# Version1.net
KiCad netlist of a schematic drawn in EAGLE
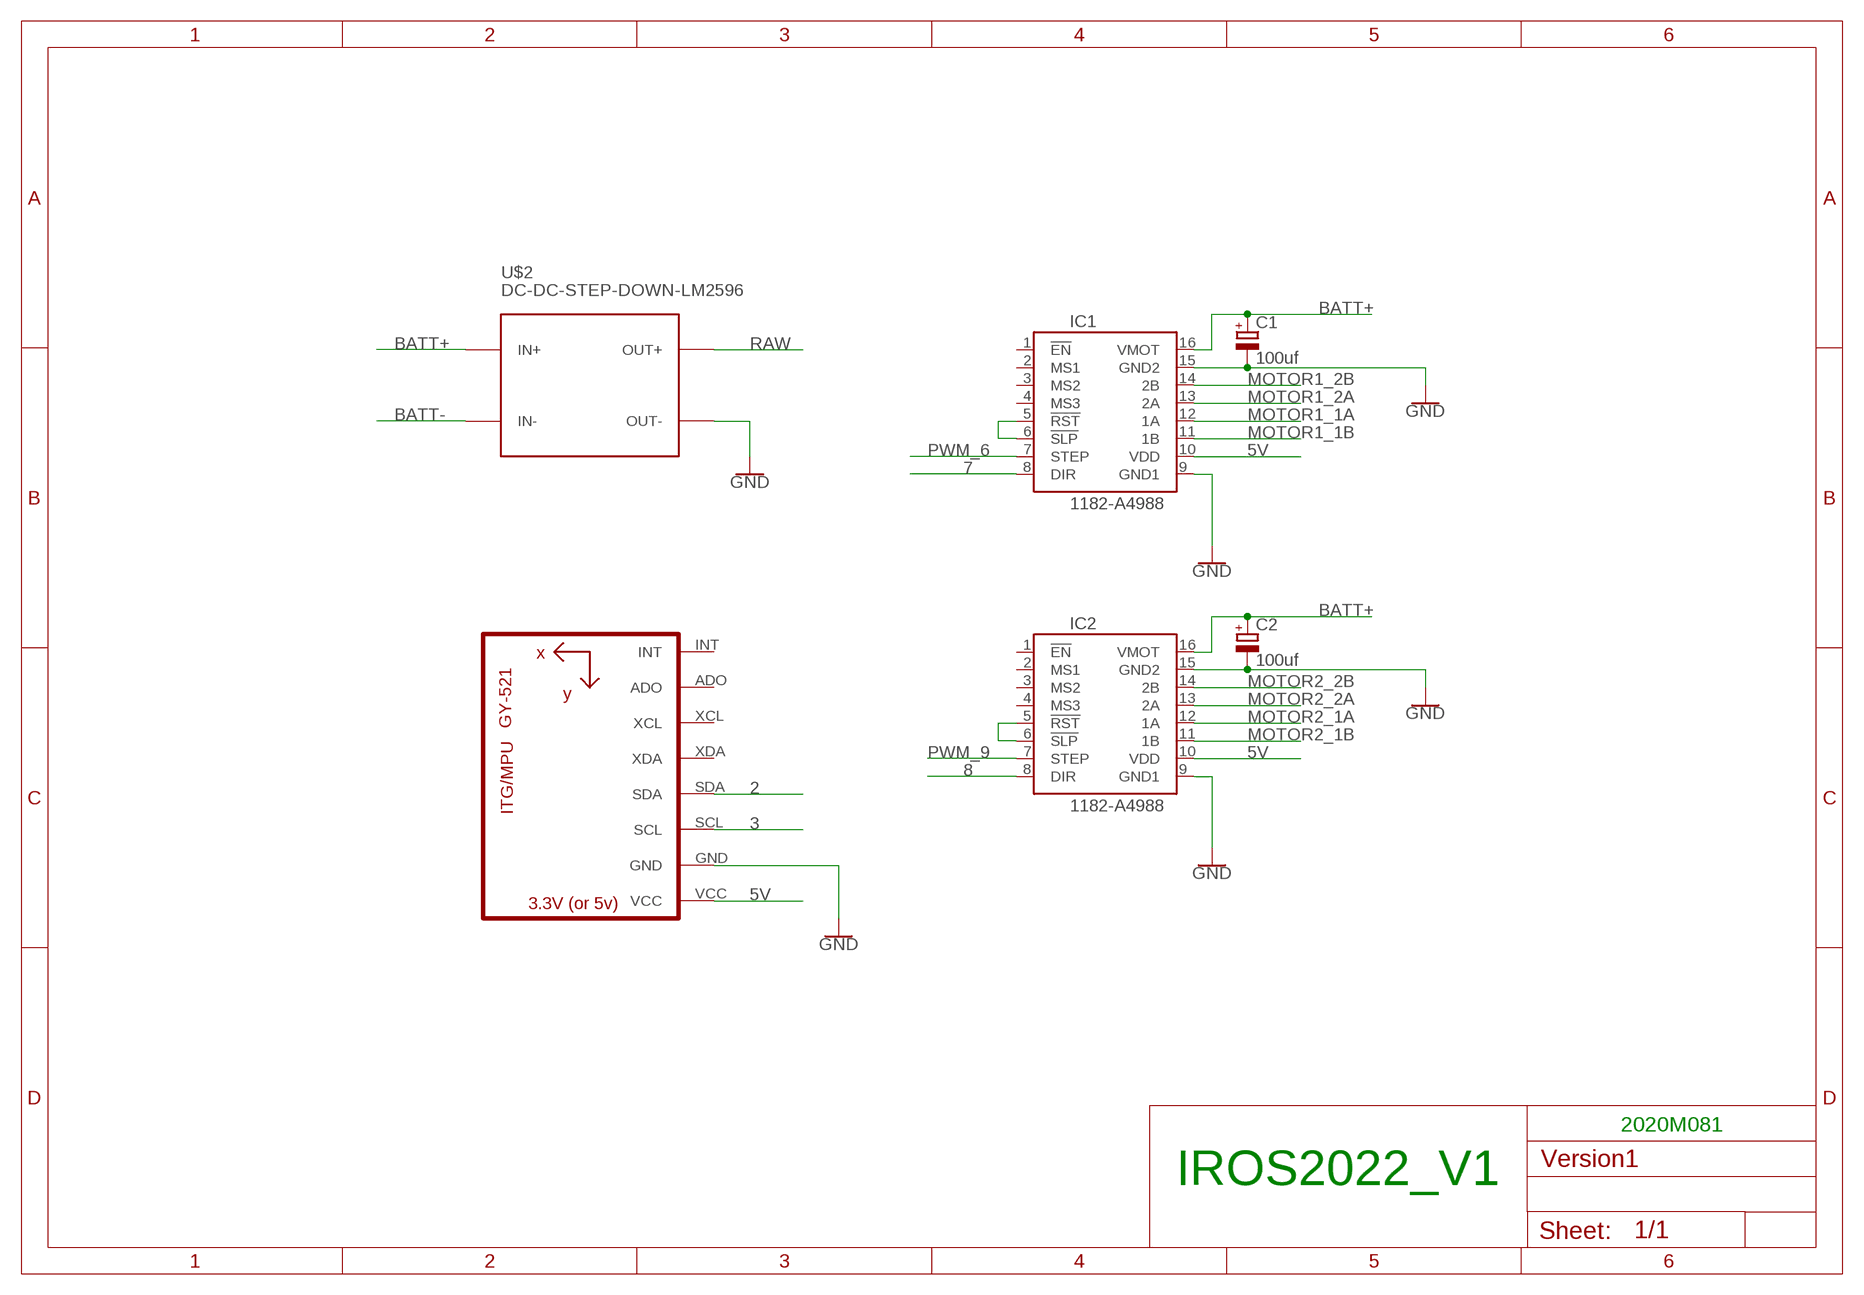
[diagram p0: schematic, sheet 1]

(export (version "E")
  (design (tool "Eeschema 10.0.6"))
  (components
    (comp (ref "C1")
      (value "100uf")
      (footprint "eagle-import:E5-10,5")
      (libsource (lib "eagle-import") (part "CPOL-EUE5-10.5"))
    )
    (comp (ref "C2")
      (value "100uf")
      (footprint "eagle-import:E5-10,5")
      (libsource (lib "eagle-import") (part "CPOL-EUE5-10.5"))
    )
    (comp (ref "IC1")
      (value "1182-A4988")
      (footprint "eagle-import:A4988")
      (libsource (lib "eagle-import") (part "1182-A4988"))
    )
    (comp (ref "IC2")
      (value "1182-A4988")
      (footprint "eagle-import:A4988")
      (libsource (lib "eagle-import") (part "1182-A4988"))
    )
    (comp (ref "U$2")
      (value "DC-DC-STEP-DOWN-LM2596")
      (footprint "eagle-import:DC-DC-STEP-DOWN-LM2596")
      (libsource (lib "eagle-import") (part "DC-DC-STEP-DOWN-LM2596"))
    )
    (comp (ref "U1")
      (value "GY-521MPU6050")
      (footprint "eagle-import:GY-521")
      (libsource (lib "eagle-import") (part "GY-521MPU6050"))
    )
  )
  (nets
    (net (code "1") (name "/2") (class "Default")
      (node (ref "U1") (pin "SDA") (pinfunction "SDA_SDA") (pintype "bidirectional"))
    )
    (net (code "2") (name "/3") (class "Default")
      (node (ref "U1") (pin "SCL") (pinfunction "SCL_SCL") (pintype "bidirectional"))
    )
    (net (code "3") (name "/5V") (class "Default")
      (node (ref "IC1") (pin "10") (pinfunction "VDD_10") (pintype "power_in"))
      (node (ref "IC2") (pin "10") (pinfunction "VDD_10") (pintype "power_in"))
      (node (ref "U1") (pin "VCC") (pinfunction "VCC_VCC") (pintype "bidirectional"))
    )
    (net (code "4") (name "/7") (class "Default")
      (node (ref "IC1") (pin "8") (pinfunction "DIR_8") (pintype "input"))
    )
    (net (code "5") (name "/8") (class "Default")
      (node (ref "IC2") (pin "8") (pinfunction "DIR_8") (pintype "input"))
    )
    (net (code "6") (name "/BATT+") (class "Default")
      (node (ref "C1") (pin "+") (pinfunction "+_+") (pintype "passive"))
      (node (ref "C2") (pin "+") (pinfunction "+_+") (pintype "passive"))
      (node (ref "IC1") (pin "16") (pinfunction "VMOT_16") (pintype "power_in"))
      (node (ref "IC2") (pin "16") (pinfunction "VMOT_16") (pintype "power_in"))
      (node (ref "U$2") (pin "IN+") (pinfunction "IN+_IN+") (pintype "bidirectional"))
    )
    (net (code "7") (name "/BATT-") (class "Default")
      (node (ref "U$2") (pin "IN-") (pinfunction "IN-_IN-") (pintype "bidirectional"))
    )
    (net (code "8") (name "/MOTOR1_1A") (class "Default")
      (node (ref "IC1") (pin "12") (pinfunction "1A_12") (pintype "output"))
    )
    (net (code "9") (name "/MOTOR1_1B") (class "Default")
      (node (ref "IC1") (pin "11") (pinfunction "1B_11") (pintype "output"))
    )
    (net (code "10") (name "/MOTOR1_2A") (class "Default")
      (node (ref "IC1") (pin "13") (pinfunction "2A_13") (pintype "output"))
    )
    (net (code "11") (name "/MOTOR1_2B") (class "Default")
      (node (ref "IC1") (pin "14") (pinfunction "2B_14") (pintype "output"))
    )
    (net (code "12") (name "/MOTOR2_1A") (class "Default")
      (node (ref "IC2") (pin "12") (pinfunction "1A_12") (pintype "output"))
    )
    (net (code "13") (name "/MOTOR2_1B") (class "Default")
      (node (ref "IC2") (pin "11") (pinfunction "1B_11") (pintype "output"))
    )
    (net (code "14") (name "/MOTOR2_2A") (class "Default")
      (node (ref "IC2") (pin "13") (pinfunction "2A_13") (pintype "output"))
    )
    (net (code "15") (name "/MOTOR2_2B") (class "Default")
      (node (ref "IC2") (pin "14") (pinfunction "2B_14") (pintype "output"))
    )
    (net (code "16") (name "/PWM_6") (class "Default")
      (node (ref "IC1") (pin "7") (pinfunction "STEP_7") (pintype "input"))
    )
    (net (code "17") (name "/PWM_9") (class "Default")
      (node (ref "IC2") (pin "7") (pinfunction "STEP_7") (pintype "input"))
    )
    (net (code "18") (name "/RAW") (class "Default")
      (node (ref "U$2") (pin "OUT+") (pinfunction "OUT+_OUT+") (pintype "bidirectional"))
    )
    (net (code "19") (name "GND") (class "Default")
      (node (ref "C1") (pin "-") (pinfunction "-_-") (pintype "passive"))
      (node (ref "C2") (pin "-") (pinfunction "-_-") (pintype "passive"))
      (node (ref "IC1") (pin "15") (pinfunction "GND2_15") (pintype "power_in"))
      (node (ref "IC1") (pin "9") (pinfunction "GND1_9") (pintype "power_in"))
      (node (ref "IC2") (pin "15") (pinfunction "GND2_15") (pintype "power_in"))
      (node (ref "IC2") (pin "9") (pinfunction "GND1_9") (pintype "power_in"))
      (node (ref "U$2") (pin "OUT-") (pinfunction "OUT-_OUT-") (pintype "bidirectional"))
      (node (ref "U1") (pin "GND") (pinfunction "GND_GND") (pintype "bidirectional"))
    )
    (net (code "20") (name "Net-(IC1-~{RST})") (class "Default")
      (node (ref "IC1") (pin "5") (pinfunction "~{RST}_5") (pintype "passive"))
      (node (ref "IC1") (pin "6") (pinfunction "~{SLP}_6") (pintype "passive"))
    )
    (net (code "21") (name "Net-(IC2-~{RST})") (class "Default")
      (node (ref "IC2") (pin "5") (pinfunction "~{RST}_5") (pintype "passive"))
      (node (ref "IC2") (pin "6") (pinfunction "~{SLP}_6") (pintype "passive"))
    )
    (net (code "22") (name "unconnected-(IC1-MS1-Pad2)") (class "Default")
      (node (ref "IC1") (pin "2") (pinfunction "MS1_2") (pintype "passive"))
    )
    (net (code "23") (name "unconnected-(IC1-MS2-Pad3)") (class "Default")
      (node (ref "IC1") (pin "3") (pinfunction "MS2_3") (pintype "passive"))
    )
    (net (code "24") (name "unconnected-(IC1-MS3-Pad4)") (class "Default")
      (node (ref "IC1") (pin "4") (pinfunction "MS3_4") (pintype "passive"))
    )
    (net (code "25") (name "unconnected-(IC1-~{EN}-Pad1)") (class "Default")
      (node (ref "IC1") (pin "1") (pinfunction "~{EN}_1") (pintype "passive"))
    )
    (net (code "26") (name "unconnected-(IC2-MS1-Pad2)") (class "Default")
      (node (ref "IC2") (pin "2") (pinfunction "MS1_2") (pintype "passive"))
    )
    (net (code "27") (name "unconnected-(IC2-MS2-Pad3)") (class "Default")
      (node (ref "IC2") (pin "3") (pinfunction "MS2_3") (pintype "passive"))
    )
    (net (code "28") (name "unconnected-(IC2-MS3-Pad4)") (class "Default")
      (node (ref "IC2") (pin "4") (pinfunction "MS3_4") (pintype "passive"))
    )
    (net (code "29") (name "unconnected-(IC2-~{EN}-Pad1)") (class "Default")
      (node (ref "IC2") (pin "1") (pinfunction "~{EN}_1") (pintype "passive"))
    )
    (net (code "30") (name "unconnected-(U1-PadADO)") (class "Default")
      (node (ref "U1") (pin "ADO") (pinfunction "ADO_ADO") (pintype "bidirectional"))
    )
    (net (code "31") (name "unconnected-(U1-PadINT)") (class "Default")
      (node (ref "U1") (pin "INT") (pinfunction "INT_INT") (pintype "bidirectional"))
    )
    (net (code "32") (name "unconnected-(U1-PadXCL)") (class "Default")
      (node (ref "U1") (pin "XCL") (pinfunction "XCL_XCL") (pintype "bidirectional"))
    )
    (net (code "33") (name "unconnected-(U1-PadXDA)") (class "Default")
      (node (ref "U1") (pin "XDA") (pinfunction "XDA_XDA") (pintype "bidirectional"))
    )
  )
)
